# I2C_Shiled.net
KiCad netlist of a schematic drawn in Altium Designer
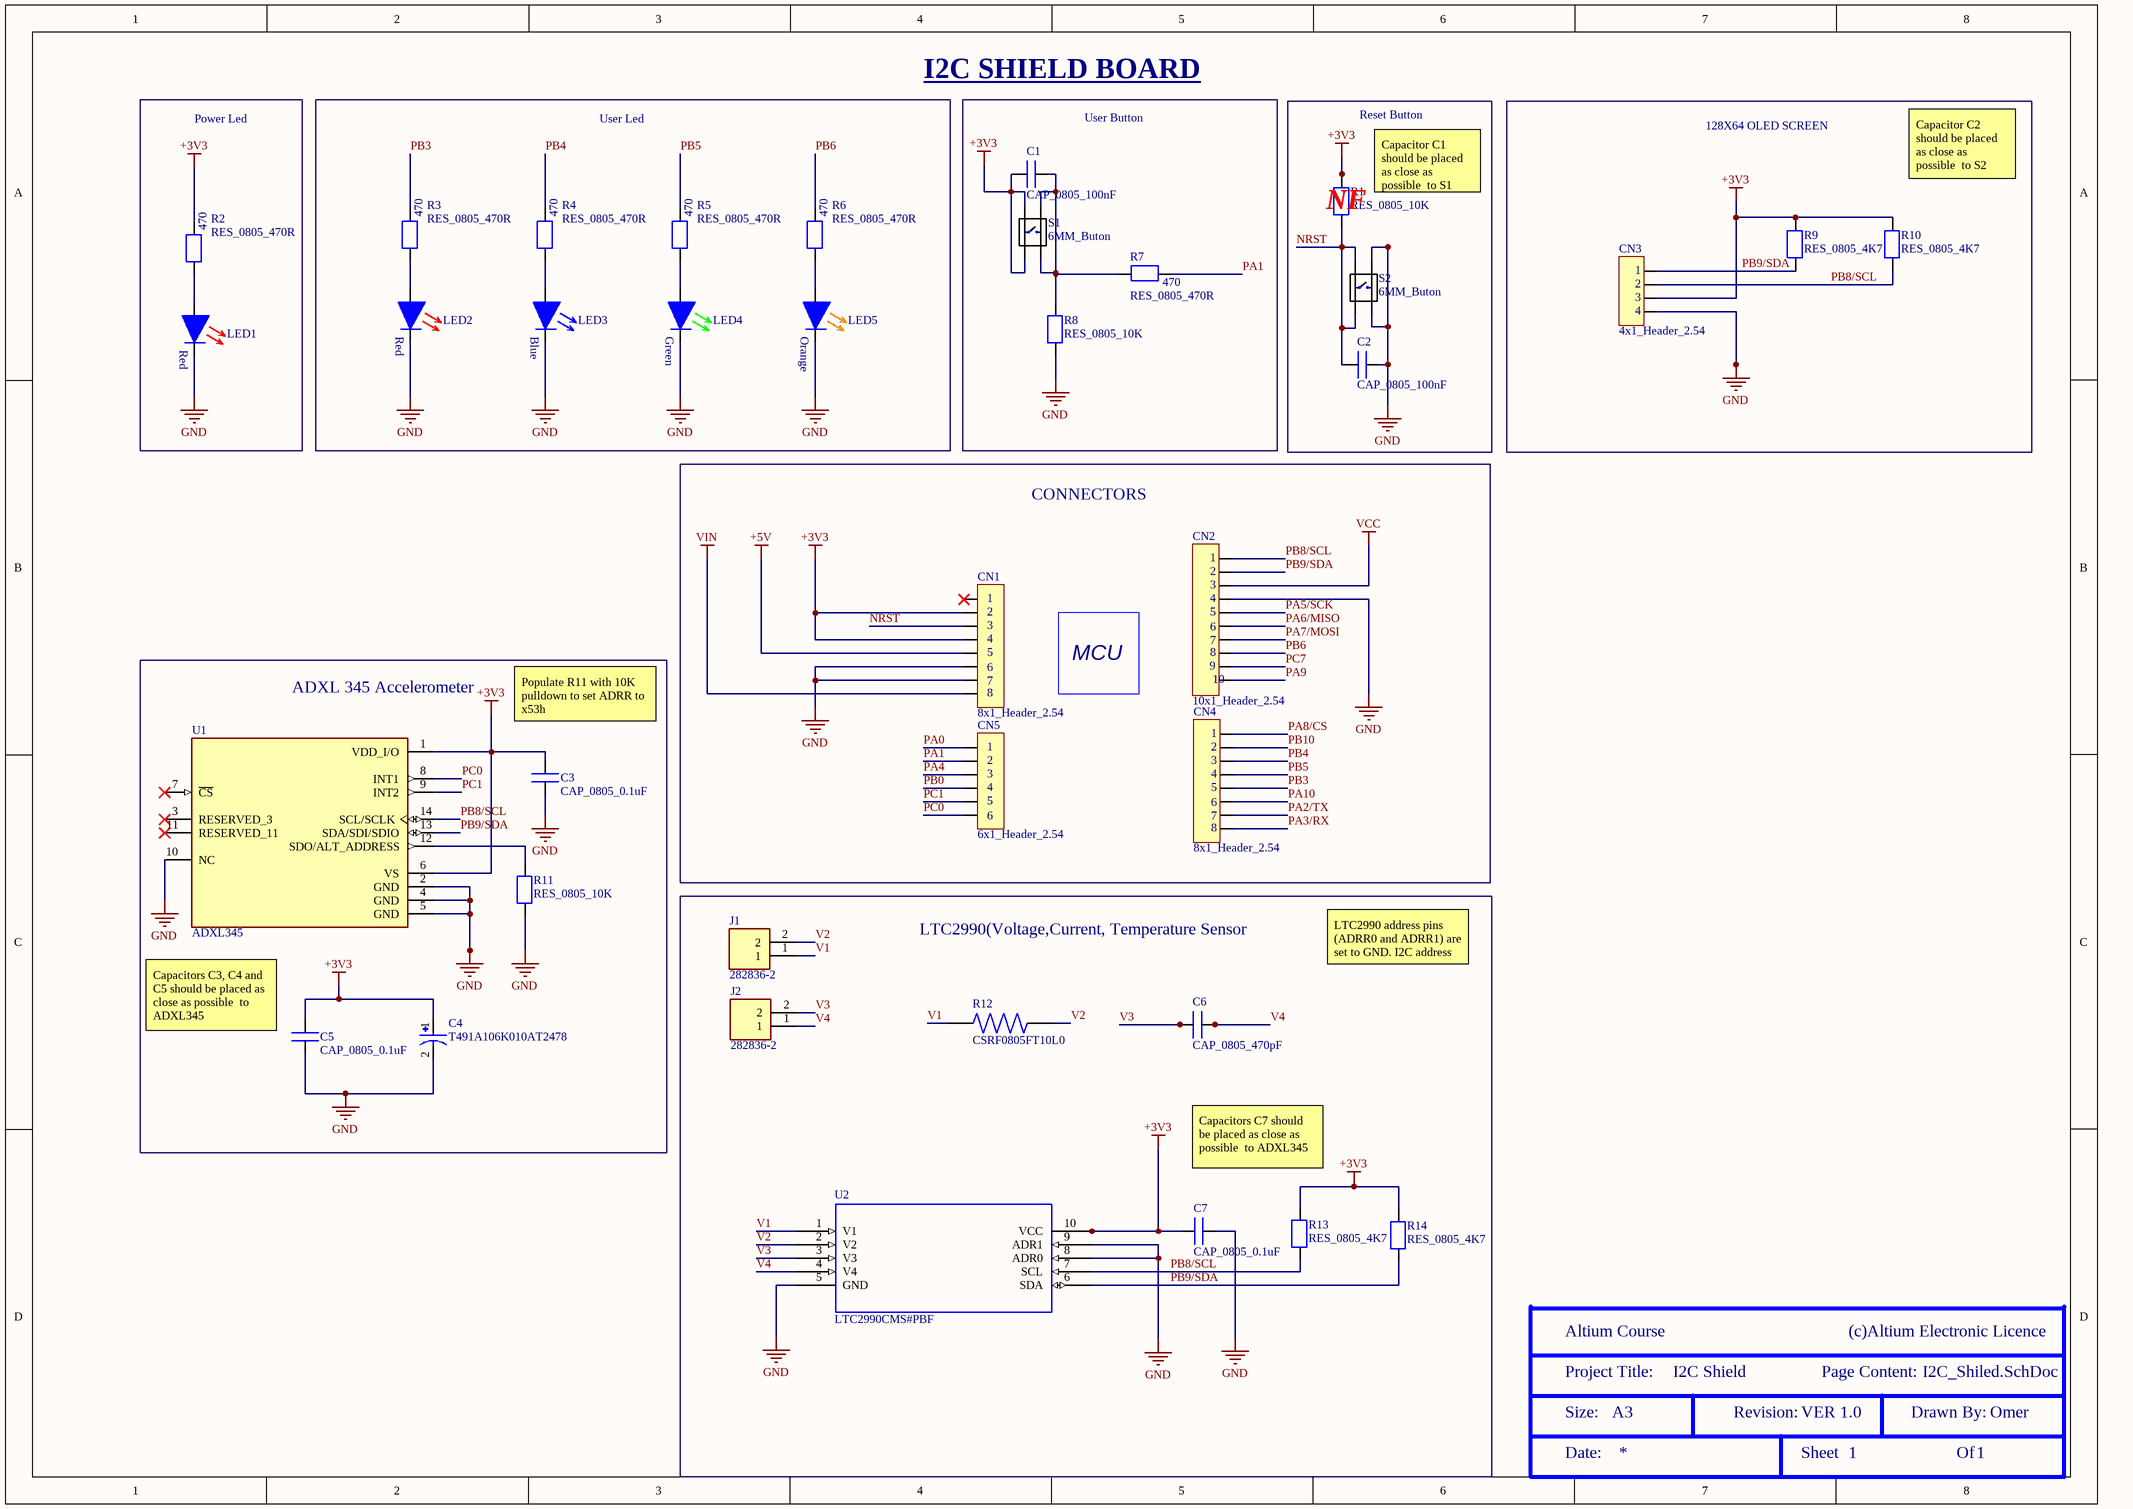
[diagram p0: I2C_Shiled.SchDoc]

(export (version "E")
  (design (tool "Eeschema 10.0.6"))
  (components
    (comp (ref "*")
      (value "Title Block")
      (fields (field (name "SIZE") "A3") (field (name "DRAWN BY") "Omer"))
      (libsource (lib "I2C_Shield") (part "Title Block"))
    )
    (comp (ref "C1")
      (value "CAP_0805_100nF")
      (footprint "CAP_0805")
      (description "0805 100nF 16VDC 10% X7R")
      (fields (field (name "TOLERANCE") "%10"))
      (libsource (lib "I2C_Shield") (part "CAP_0805_100nF"))
    )
    (comp (ref "C2")
      (value "CAP_0805_100nF")
      (footprint "CAP_0805")
      (description "0805 100nF 16VDC 10% X7R")
      (fields (field (name "TOLERANCE") "%10"))
      (libsource (lib "I2C_Shield") (part "CAP_0805_100nF"))
    )
    (comp (ref "C3")
      (value "CAP_0805_0.1uF")
      (footprint "CAP_0805")
      (description "0805 0.1uF 16VDC 10% X7R")
      (fields (field (name "TOLERANCE") "%10"))
      (libsource (lib "I2C_Shield") (part "CAP_0805_0.1uF"))
    )
    (comp (ref "C4")
      (value "T491A106K010AT2478")
      (footprint "CAPMP3216X180N")
      (description "10 ÂµF Molded Tantalum Capacitors 10 V 1206 (3216 Metric) 3.8Ohm")
      (fields (field (name "MF") "KEMET"))
      (libsource (lib "T491A106K010AT2478") (part "T491A106K010AT2478"))
    )
    (comp (ref "C5")
      (value "CAP_0805_0.1uF")
      (footprint "CAP_0805")
      (description "0805 0.1uF 16VDC 10% X7R")
      (fields (field (name "TOLERANCE") "%10"))
      (libsource (lib "I2C_Shield") (part "CAP_0805_0.1uF"))
    )
    (comp (ref "C6")
      (value "CAP_0805_470pF")
      (footprint "CAP_0805")
      (description "0805 470pF 16VDC 10% X7R")
      (fields (field (name "TOLERANCE") "%10"))
      (libsource (lib "I2C_Shield") (part "CAP_0805_470pF"))
    )
    (comp (ref "C7")
      (value "CAP_0805_0.1uF")
      (footprint "CAP_0805")
      (description "0805 0.1uF 16VDC 10% X7R")
      (fields (field (name "TOLERANCE") "%10"))
      (libsource (lib "I2C_Shield") (part "CAP_0805_0.1uF"))
    )
    (comp (ref "CN1")
      (value "8x1_Header_2.54")
      (footprint "8x1_2.54MM_HEADER")
      (description "Arduino Boards Connector")
      (libsource (lib "") (part "8x1_Header_2.54_1"))
    )
    (comp (ref "CN2")
      (value "10x1_Header_2.54")
      (footprint "10x1_2.54MM_HEADER")
      (description "Arduino Boards Connector")
      (libsource (lib "I2C_Shield") (part "10x1_Header_2.54"))
    )
    (comp (ref "CN3")
      (value "4x1_Header_2.54")
      (footprint "4x1_2.54MM_HEADER")
      (description "OLED SCREEN HEADER")
      (libsource (lib "I2C_Shield") (part "4x1_Header_2.54"))
    )
    (comp (ref "CN4")
      (value "8x1_Header_2.54")
      (footprint "8x1_2.54MM_HEADER")
      (description "Arduino Boards Connector")
      (libsource (lib "I2C_Shield") (part "8x1_Header_2.54"))
    )
    (comp (ref "CN5")
      (value "6x1_Header_2.54")
      (footprint "6x1_2.54MM_HEADER")
      (description "Arduino Boards Connector")
      (libsource (lib "I2C_Shield") (part "6x1_Header_2.54"))
    )
    (comp (ref "J1")
      (value "282836-2")
      (footprint "TE_282836-2")
      (description "Connector, Terminal Block; Wire Receptacle; 2 Pos.; 16-30 AWG; 0.197 in. CL; Sid")
      (fields (field (name "MF") "TE Connectivity"))
      (libsource (lib "terminalblock-2") (part "282836-2"))
    )
    (comp (ref "J2")
      (value "282836-2")
      (footprint "TE_282836-2")
      (description "Connector, Terminal Block; Wire Receptacle; 2 Pos.; 16-30 AWG; 0.197 in. CL; Sid")
      (fields (field (name "MF") "TE Connectivity"))
      (libsource (lib "terminalblock-2") (part "282836-2"))
    )
    (comp (ref "LED1")
      (value "DIODE_0805_Red")
      (footprint "LED_0805")
      (description "LED SMD 0805 RED 160-210mcd")
      (fields
        (field (name "MANUFACTURER") "https://www.ozdisan.com/p/sinyal-ledler-tek-renkli-361/honglitronic-hl-psc-2012u51gc-471651")
      )
      (libsource (lib "I2C_Shield") (part "LED_0805_Red"))
    )
    (comp (ref "LED2")
      (value "DIODE_0805_Red")
      (footprint "LED_0805")
      (description "LED SMD 0805 RED 160-210mcd")
      (fields
        (field (name "MANUFACTURER") "https://www.ozdisan.com/p/sinyal-ledler-tek-renkli-361/honglitronic-hl-psc-2012u51gc-471651")
      )
      (libsource (lib "I2C_Shield") (part "LED_0805_Red"))
    )
    (comp (ref "LED3")
      (value "DIODE_0805_Blue")
      (footprint "LED_0805")
      (description "LED SMD 0805 BLUE 160-210mcd")
      (fields
        (field (name "MANUFACTURER") "https://www.ozdisan.com/p/sinyal-ledler-tek-renkli-361/honglitronic-hl-psc-2012u51gc-471651")
      )
      (libsource (lib "I2C_Shield") (part "LED_0805_Blue"))
    )
    (comp (ref "LED4")
      (value "DIODE_0805_Green")
      (footprint "LED_0805")
      (description "LED SMD 0805 GREEN160-210mcd")
      (fields
        (field (name "MANUFACTURER") "https://www.ozdisan.com/p/sinyal-ledler-tek-renkli-361/honglitronic-hl-psc-2012u51gc-471651")
      )
      (libsource (lib "I2C_Shield") (part "LED_0805_Green"))
    )
    (comp (ref "LED5")
      (value "DIODE_0805_Orange")
      (footprint "LED_0805")
      (description "LED SMD 0805 ORANGE 160-210mcd")
      (fields
        (field (name "MANUFACTURER") "https://www.ozdisan.com/p/sinyal-ledler-tek-renkli-361/honglitronic-hl-psc-2012u51gc-471651")
      )
      (libsource (lib "I2C_Shield") (part "LED_0805_Orange"))
    )
    (comp (ref "R1")
      (value "RES_0805_10K")
      (footprint "RES_0805")
      (description "0805 10K Ohms 5%")
      (fields (field (name "TOLERANCE") "%5"))
      (libsource (lib "I2C_Shield") (part "RES_0805_10K"))
    )
    (comp (ref "R2")
      (value "RES_0805_470R")
      (footprint "RES_0805")
      (description "0805 470 Ohms 5%")
      (fields (field (name "TOLERANCE") "%5"))
      (libsource (lib "I2C_Shield") (part "RES_0805_470R"))
    )
    (comp (ref "R3")
      (value "RES_0805_470R")
      (footprint "RES_0805")
      (description "0805 470 Ohms 5%")
      (fields (field (name "TOLERANCE") "%5"))
      (libsource (lib "I2C_Shield") (part "RES_0805_470R"))
    )
    (comp (ref "R4")
      (value "RES_0805_470R")
      (footprint "RES_0805")
      (description "0805 470 Ohms 5%")
      (fields (field (name "TOLERANCE") "%5"))
      (libsource (lib "I2C_Shield") (part "RES_0805_470R"))
    )
    (comp (ref "R5")
      (value "RES_0805_470R")
      (footprint "RES_0805")
      (description "0805 470 Ohms 5%")
      (fields (field (name "TOLERANCE") "%5"))
      (libsource (lib "I2C_Shield") (part "RES_0805_470R"))
    )
    (comp (ref "R6")
      (value "RES_0805_470R")
      (footprint "RES_0805")
      (description "0805 470 Ohms 5%")
      (fields (field (name "TOLERANCE") "%5"))
      (libsource (lib "I2C_Shield") (part "RES_0805_470R"))
    )
    (comp (ref "R7")
      (value "RES_0805_470R")
      (footprint "RES_0805")
      (description "0805 470 Ohms 5%")
      (fields (field (name "TOLERANCE") "%5"))
      (libsource (lib "I2C_Shield") (part "RES_0805_470R"))
    )
    (comp (ref "R8")
      (value "RES_0805_10K")
      (footprint "RES_0805")
      (description "0805 10K Ohms 5%")
      (fields (field (name "TOLERANCE") "%5"))
      (libsource (lib "I2C_Shield") (part "RES_0805_10K"))
    )
    (comp (ref "R9")
      (value "RES_0805_4K7")
      (footprint "RES_0805")
      (description "0805 4K7 Ohms 5%")
      (fields (field (name "TOLERANCE") "%5"))
      (libsource (lib "I2C_Shield") (part "RES_0805_4K7"))
    )
    (comp (ref "R10")
      (value "RES_0805_4K7")
      (footprint "RES_0805")
      (description "0805 4K7 Ohms 5%")
      (fields (field (name "TOLERANCE") "%5"))
      (libsource (lib "I2C_Shield") (part "RES_0805_4K7"))
    )
    (comp (ref "R11")
      (value "RES_0805_10K")
      (footprint "RES_0805")
      (description "0805 10K Ohms 5%")
      (fields (field (name "TOLERANCE") "%5"))
      (libsource (lib "I2C_Shield") (part "RES_0805_10K"))
    )
    (comp (ref "R12")
      (value "CSRF0805FT10L0")
      (footprint "RESC2113X85N")
      (fields (field (name "MF") "Stackpole Electronics"))
      (libsource (lib "CSRF0805FT10L0") (part "CSRF0805FT10L0"))
    )
    (comp (ref "R13")
      (value "RES_0805_4K7")
      (footprint "RES_0805")
      (description "0805 4K7 Ohms 5%")
      (fields (field (name "TOLERANCE") "%5"))
      (libsource (lib "I2C_Shield") (part "RES_0805_4K7"))
    )
    (comp (ref "R14")
      (value "RES_0805_4K7")
      (footprint "RES_0805")
      (description "0805 4K7 Ohms 5%")
      (fields (field (name "TOLERANCE") "%5"))
      (libsource (lib "I2C_Shield") (part "RES_0805_4K7"))
    )
    (comp (ref "S1")
      (value "6MM_Buton")
      (footprint "6MM_TACTILE_SWITCH")
      (description "SWITCH TACT 12.00x12.00 6.00mm")
      (libsource (lib "I2C_Shield") (part "6MM_Buton"))
    )
    (comp (ref "S2")
      (value "6MM_Buton")
      (footprint "6MM_TACTILE_SWITCH")
      (description "SWITCH TACT 12.00x12.00 6.00mm")
      (libsource (lib "I2C_Shield") (part "6MM_Buton"))
    )
    (comp (ref "U1")
      (value "ADXL345")
      (footprint "PQFN80P500X300X100-14N")
      (description "Accelerometer X, Y, Z Axis ±2g, 4g, 8g, 16g 0.05Hz ~ 1.6kHz 14-LGA (3x5)")
      (fields (field (name "MF") "Analog Devices, Inc."))
      (libsource (lib "ADXL345") (part "ADXL345"))
    )
    (comp (ref "U2")
      (value "LTC2990CMS#PBF")
      (footprint "MSOP-10_MS")
      (fields (field (name "MF") "Analog Devices"))
      (libsource (lib "LTC2990CMS_PBF") (part "LTC2990CMS#PBF"))
    )
  )
  (nets
    (net (code "1") (name "+3V3") (class "Default")
      (node (ref "C1") (pin "1") (pinfunction "1_1") (pintype "passive"))
      (node (ref "C3") (pin "2") (pinfunction "2_2") (pintype "passive"))
      (node (ref "C4") (pin "1") (pinfunction "1_1") (pintype "passive"))
      (node (ref "C5") (pin "2") (pinfunction "2_2") (pintype "passive"))
      (node (ref "C7") (pin "1") (pinfunction "1_1") (pintype "passive"))
      (node (ref "CN1") (pin "02") (pinfunction "02_02") (pintype "passive"))
      (node (ref "CN1") (pin "04") (pinfunction "04_04") (pintype "passive"))
      (node (ref "CN3") (pin "03") (pinfunction "03_03") (pintype "passive"))
      (node (ref "R1") (pin "2") (pinfunction "2_2") (pintype "passive"))
      (node (ref "R10") (pin "2") (pinfunction "2_2") (pintype "passive"))
      (node (ref "R13") (pin "2") (pinfunction "2_2") (pintype "passive"))
      (node (ref "R14") (pin "2") (pinfunction "2_2") (pintype "passive"))
      (node (ref "R2") (pin "2") (pinfunction "2_2") (pintype "passive"))
      (node (ref "R9") (pin "2") (pinfunction "2_2") (pintype "passive"))
      (node (ref "S1") (pin "1") (pinfunction "2_1") (pintype "passive"))
      (node (ref "S1") (pin "3") (pinfunction "0_3") (pintype "passive"))
      (node (ref "U1") (pin "1") (pinfunction "VDD_I/O_1") (pintype "power_in"))
      (node (ref "U1") (pin "6") (pinfunction "VS_6") (pintype "power_in"))
      (node (ref "U2") (pin "10") (pinfunction "VCC_10") (pintype "power_in"))
    )
    (net (code "2") (name "+5V") (class "Default")
      (node (ref "CN1") (pin "05") (pinfunction "05_05") (pintype "passive"))
    )
    (net (code "3") (name "/NRST") (class "Default")
      (node (ref "C2") (pin "1") (pinfunction "1_1") (pintype "passive"))
      (node (ref "CN1") (pin "03") (pinfunction "03_03") (pintype "passive"))
      (node (ref "R1") (pin "1") (pinfunction "1_1") (pintype "passive"))
      (node (ref "S2") (pin "1") (pinfunction "2_1") (pintype "passive"))
      (node (ref "S2") (pin "3") (pinfunction "0_3") (pintype "passive"))
    )
    (net (code "4") (name "/PA0") (class "Default")
      (node (ref "CN5") (pin "01") (pinfunction "01_01") (pintype "passive"))
    )
    (net (code "5") (name "/PA1") (class "Default")
      (node (ref "CN5") (pin "02") (pinfunction "02_02") (pintype "passive"))
      (node (ref "R7") (pin "2") (pinfunction "2_2") (pintype "passive"))
    )
    (net (code "6") (name "/PA2{slash}TX") (class "Default")
      (node (ref "CN4") (pin "07") (pinfunction "07_07") (pintype "passive"))
    )
    (net (code "7") (name "/PA3{slash}RX") (class "Default")
      (node (ref "CN4") (pin "08") (pinfunction "08_08") (pintype "passive"))
    )
    (net (code "8") (name "/PA4") (class "Default")
      (node (ref "CN5") (pin "03") (pinfunction "03_03") (pintype "passive"))
    )
    (net (code "9") (name "/PA5{slash}SCK") (class "Default")
      (node (ref "CN2") (pin "05") (pinfunction "05_05") (pintype "passive"))
    )
    (net (code "10") (name "/PA6{slash}MISO") (class "Default")
      (node (ref "CN2") (pin "06") (pinfunction "06_06") (pintype "passive"))
    )
    (net (code "11") (name "/PA7{slash}MOSI") (class "Default")
      (node (ref "CN2") (pin "07") (pinfunction "07_07") (pintype "passive"))
    )
    (net (code "12") (name "/PA8{slash}CS") (class "Default")
      (node (ref "CN4") (pin "01") (pinfunction "01_01") (pintype "passive"))
    )
    (net (code "13") (name "/PA9") (class "Default")
      (node (ref "CN2") (pin "10") (pinfunction "10_10") (pintype "passive"))
    )
    (net (code "14") (name "/PA10") (class "Default")
      (node (ref "CN4") (pin "06") (pinfunction "06_06") (pintype "passive"))
    )
    (net (code "15") (name "/PB0") (class "Default")
      (node (ref "CN5") (pin "04") (pinfunction "04_04") (pintype "passive"))
    )
    (net (code "16") (name "/PB3") (class "Default")
      (node (ref "CN4") (pin "05") (pinfunction "05_05") (pintype "passive"))
      (node (ref "R3") (pin "2") (pinfunction "2_2") (pintype "passive"))
    )
    (net (code "17") (name "/PB4") (class "Default")
      (node (ref "CN4") (pin "03") (pinfunction "03_03") (pintype "passive"))
      (node (ref "R4") (pin "2") (pinfunction "2_2") (pintype "passive"))
    )
    (net (code "18") (name "/PB5") (class "Default")
      (node (ref "CN4") (pin "04") (pinfunction "04_04") (pintype "passive"))
      (node (ref "R5") (pin "2") (pinfunction "2_2") (pintype "passive"))
    )
    (net (code "19") (name "/PB6") (class "Default")
      (node (ref "CN2") (pin "08") (pinfunction "08_08") (pintype "passive"))
      (node (ref "R6") (pin "2") (pinfunction "2_2") (pintype "passive"))
    )
    (net (code "20") (name "/PB8{slash}SCL") (class "Default")
      (node (ref "CN2") (pin "01") (pinfunction "01_01") (pintype "passive"))
      (node (ref "CN3") (pin "02") (pinfunction "02_02") (pintype "passive"))
      (node (ref "R10") (pin "1") (pinfunction "1_1") (pintype "passive"))
      (node (ref "R13") (pin "1") (pinfunction "1_1") (pintype "passive"))
      (node (ref "U1") (pin "14") (pinfunction "SCL/SCLK_14") (pintype "bidirectional"))
      (node (ref "U2") (pin "7") (pinfunction "SCL_7") (pintype "input"))
    )
    (net (code "21") (name "/PB9{slash}SDA") (class "Default")
      (node (ref "CN2") (pin "02") (pinfunction "02_02") (pintype "passive"))
      (node (ref "CN3") (pin "01") (pinfunction "01_01") (pintype "passive"))
      (node (ref "R14") (pin "1") (pinfunction "1_1") (pintype "passive"))
      (node (ref "R9") (pin "1") (pinfunction "1_1") (pintype "passive"))
      (node (ref "U1") (pin "13") (pinfunction "SDA/SDI/SDIO_13") (pintype "bidirectional"))
      (node (ref "U2") (pin "6") (pinfunction "SDA_6") (pintype "bidirectional"))
    )
    (net (code "22") (name "/PB10") (class "Default")
      (node (ref "CN4") (pin "02") (pinfunction "02_02") (pintype "passive"))
    )
    (net (code "23") (name "/PC0") (class "Default")
      (node (ref "CN5") (pin "06") (pinfunction "06_06") (pintype "passive"))
      (node (ref "U1") (pin "8") (pinfunction "INT1_8") (pintype "output"))
    )
    (net (code "24") (name "/PC1") (class "Default")
      (node (ref "CN5") (pin "05") (pinfunction "05_05") (pintype "passive"))
      (node (ref "U1") (pin "9") (pinfunction "INT2_9") (pintype "output"))
    )
    (net (code "25") (name "/PC7") (class "Default")
      (node (ref "CN2") (pin "09") (pinfunction "09_09") (pintype "passive"))
    )
    (net (code "26") (name "/V1") (class "Default")
      (node (ref "J1") (pin "1") (pinfunction "1_1") (pintype "passive"))
      (node (ref "R12") (pin "1") (pinfunction "1_1") (pintype "passive"))
      (node (ref "U2") (pin "1") (pinfunction "V1_1") (pintype "input"))
    )
    (net (code "27") (name "/V2") (class "Default")
      (node (ref "J1") (pin "2") (pinfunction "2_2") (pintype "passive"))
      (node (ref "R12") (pin "2") (pinfunction "2_2") (pintype "passive"))
      (node (ref "U2") (pin "2") (pinfunction "V2_2") (pintype "input"))
    )
    (net (code "28") (name "/V3") (class "Default")
      (node (ref "C6") (pin "1") (pinfunction "1_1") (pintype "passive"))
      (node (ref "J2") (pin "2") (pinfunction "2_2") (pintype "passive"))
      (node (ref "U2") (pin "3") (pinfunction "V3_3") (pintype "input"))
    )
    (net (code "29") (name "/V4") (class "Default")
      (node (ref "C6") (pin "2") (pinfunction "2_2") (pintype "passive"))
      (node (ref "J2") (pin "1") (pinfunction "1_1") (pintype "passive"))
      (node (ref "U2") (pin "4") (pinfunction "V4_4") (pintype "input"))
    )
    (net (code "30") (name "GND") (class "Default")
      (node (ref "C2") (pin "2") (pinfunction "2_2") (pintype "passive"))
      (node (ref "C3") (pin "1") (pinfunction "1_1") (pintype "passive"))
      (node (ref "C4") (pin "2") (pinfunction "2_2") (pintype "passive"))
      (node (ref "C5") (pin "1") (pinfunction "1_1") (pintype "passive"))
      (node (ref "C7") (pin "2") (pinfunction "2_2") (pintype "passive"))
      (node (ref "CN1") (pin "06") (pinfunction "06_06") (pintype "passive"))
      (node (ref "CN1") (pin "07") (pinfunction "07_07") (pintype "passive"))
      (node (ref "CN2") (pin "04") (pinfunction "04_04") (pintype "passive"))
      (node (ref "CN3") (pin "04") (pinfunction "04_04") (pintype "passive"))
      (node (ref "LED1") (pin "C") (pinfunction "1_C") (pintype "passive"))
      (node (ref "LED2") (pin "C") (pinfunction "1_C") (pintype "passive"))
      (node (ref "LED3") (pin "C") (pinfunction "1_C") (pintype "passive"))
      (node (ref "LED4") (pin "C") (pinfunction "1_C") (pintype "passive"))
      (node (ref "LED5") (pin "C") (pinfunction "1_C") (pintype "passive"))
      (node (ref "R11") (pin "1") (pinfunction "1_1") (pintype "passive"))
      (node (ref "R8") (pin "1") (pinfunction "1_1") (pintype "passive"))
      (node (ref "S2") (pin "2") (pinfunction "3_2") (pintype "passive"))
      (node (ref "S2") (pin "4") (pinfunction "1_4") (pintype "passive"))
      (node (ref "U1") (pin "10") (pinfunction "NC_10") (pintype "passive"))
      (node (ref "U1") (pin "2") (pinfunction "GND_2") (pintype "power_in"))
      (node (ref "U1") (pin "4") (pinfunction "GND_4") (pintype "power_in"))
      (node (ref "U1") (pin "5") (pinfunction "GND_5") (pintype "power_in"))
      (node (ref "U2") (pin "5") (pinfunction "GND_5") (pintype "power_in"))
      (node (ref "U2") (pin "8") (pinfunction "ADR0_8") (pintype "input"))
      (node (ref "U2") (pin "9") (pinfunction "ADR1_9") (pintype "input"))
    )
    (net (code "31") (name "Net-(LED1-0)") (class "Default")
      (node (ref "LED1") (pin "A") (pinfunction "0_A") (pintype "passive"))
      (node (ref "R2") (pin "1") (pinfunction "1_1") (pintype "passive"))
    )
    (net (code "32") (name "Net-(LED2-0)") (class "Default")
      (node (ref "LED2") (pin "A") (pinfunction "0_A") (pintype "passive"))
      (node (ref "R3") (pin "1") (pinfunction "1_1") (pintype "passive"))
    )
    (net (code "33") (name "Net-(LED3-0)") (class "Default")
      (node (ref "LED3") (pin "A") (pinfunction "0_A") (pintype "passive"))
      (node (ref "R4") (pin "1") (pinfunction "1_1") (pintype "passive"))
    )
    (net (code "34") (name "Net-(LED4-0)") (class "Default")
      (node (ref "LED4") (pin "A") (pinfunction "0_A") (pintype "passive"))
      (node (ref "R5") (pin "1") (pinfunction "1_1") (pintype "passive"))
    )
    (net (code "35") (name "Net-(LED5-0)") (class "Default")
      (node (ref "LED5") (pin "A") (pinfunction "0_A") (pintype "passive"))
      (node (ref "R6") (pin "1") (pinfunction "1_1") (pintype "passive"))
    )
    (net (code "36") (name "Net-(S1-1)") (class "Default")
      (node (ref "C1") (pin "2") (pinfunction "2_2") (pintype "passive"))
      (node (ref "R7") (pin "1") (pinfunction "1_1") (pintype "passive"))
      (node (ref "R8") (pin "2") (pinfunction "2_2") (pintype "passive"))
      (node (ref "S1") (pin "2") (pinfunction "3_2") (pintype "passive"))
      (node (ref "S1") (pin "4") (pinfunction "1_4") (pintype "passive"))
    )
    (net (code "37") (name "Net-(U1-SDO{slash}ALT_ADDRESS)") (class "Default")
      (node (ref "R11") (pin "2") (pinfunction "2_2") (pintype "passive"))
      (node (ref "U1") (pin "12") (pinfunction "SDO/ALT_ADDRESS_12") (pintype "output"))
    )
    (net (code "38") (name "VCC") (class "Default")
      (node (ref "CN2") (pin "03") (pinfunction "03_03") (pintype "passive"))
    )
    (net (code "39") (name "VIN") (class "Default")
      (node (ref "CN1") (pin "08") (pinfunction "08_08") (pintype "passive"))
    )
    (net (code "40") (name "unconnected-(CN1-Pad01)") (class "Default")
      (node (ref "CN1") (pin "01") (pinfunction "01_01") (pintype "passive+no_connect"))
    )
    (net (code "41") (name "unconnected-(U1-RESERVED_3-Pad3)") (class "Default")
      (node (ref "U1") (pin "3") (pinfunction "RESERVED_3_3") (pintype "passive+no_connect"))
    )
    (net (code "42") (name "unconnected-(U1-RESERVED_11-Pad11)") (class "Default")
      (node (ref "U1") (pin "11") (pinfunction "RESERVED_11_11") (pintype "passive+no_connect"))
    )
    (net (code "43") (name "unconnected-(U1-~{CS}-Pad7)") (class "Default")
      (node (ref "U1") (pin "7") (pinfunction "~{CS}_7") (pintype "input+no_connect"))
    )
  )
)
